# Sensor_ExpandBoard_W25Q64.net
KiCad netlist of a schematic drawn in Altium Designer
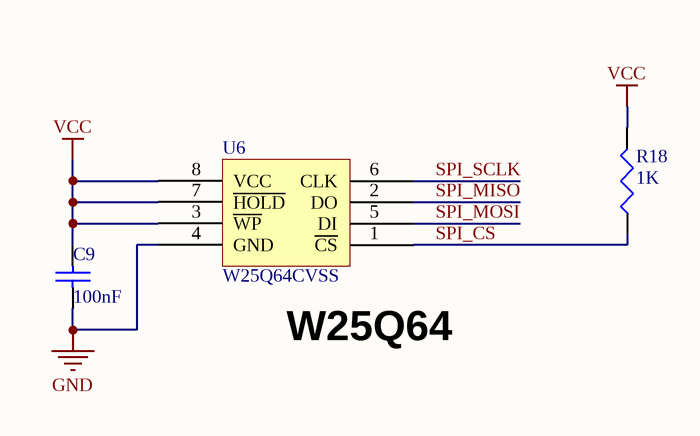
[diagram p0: Sensor_ExpandBoard_W25Q64.SchDoc]

(export (version "E")
  (design (tool "Eeschema 10.0.6"))
  (components
    (comp (ref "C9")
      (value "100nF")
      (footprint "0603-2")
      (description "无极性电容")
      (fields (field (name "PUBLISHER") "Altium Limited"))
      (libsource (lib "Fszhang") (part "Cap"))
    )
    (comp (ref "R18")
      (value "1K")
      (footprint "R0603")
      (description "Resistor")
      (fields (field (name "PUBLISHER") "Altium Limited"))
      (libsource (lib "step") (part "Res"))
    )
    (comp (ref "U6")
      (value "W25Q64CVSS")
      (footprint "SOIC8")
      (description "Quad SPI Flash,64Mb,SOIC8")
      (libsource (lib "Sensor") (part "W25Q64"))
    )
  )
  (nets
    (net (code "1") (name "/SPI_MISO") (class "Default")
      (node (ref "U6") (pin "2") (pinfunction "DO_2") (pintype "passive"))
    )
    (net (code "2") (name "/SPI_MOSI") (class "Default")
      (node (ref "U6") (pin "5") (pinfunction "DI_5") (pintype "passive"))
    )
    (net (code "3") (name "/SPI_SCLK") (class "Default")
      (node (ref "U6") (pin "6") (pinfunction "CLK_6") (pintype "passive"))
    )
    (net (code "4") (name "/SPI_~{CS}") (class "Default")
      (node (ref "R18") (pin "1") (pinfunction "1_1") (pintype "passive"))
      (node (ref "U6") (pin "1") (pinfunction "~{CS}_1") (pintype "passive"))
    )
    (net (code "5") (name "GND") (class "Default")
      (node (ref "C9") (pin "2") (pinfunction "2_2") (pintype "passive"))
      (node (ref "U6") (pin "4") (pinfunction "GND_4") (pintype "passive"))
    )
    (net (code "6") (name "VCC") (class "Default")
      (node (ref "C9") (pin "1") (pinfunction "1_1") (pintype "passive"))
      (node (ref "R18") (pin "2") (pinfunction "2_2") (pintype "passive"))
      (node (ref "U6") (pin "3") (pinfunction "~{WP}_3") (pintype "passive"))
      (node (ref "U6") (pin "7") (pinfunction "~{HOLD}_7") (pintype "passive"))
      (node (ref "U6") (pin "8") (pinfunction "VCC_8") (pintype "passive"))
    )
  )
)
